# Load_Testbed.net
KiCad netlist of a schematic drawn in EAGLE
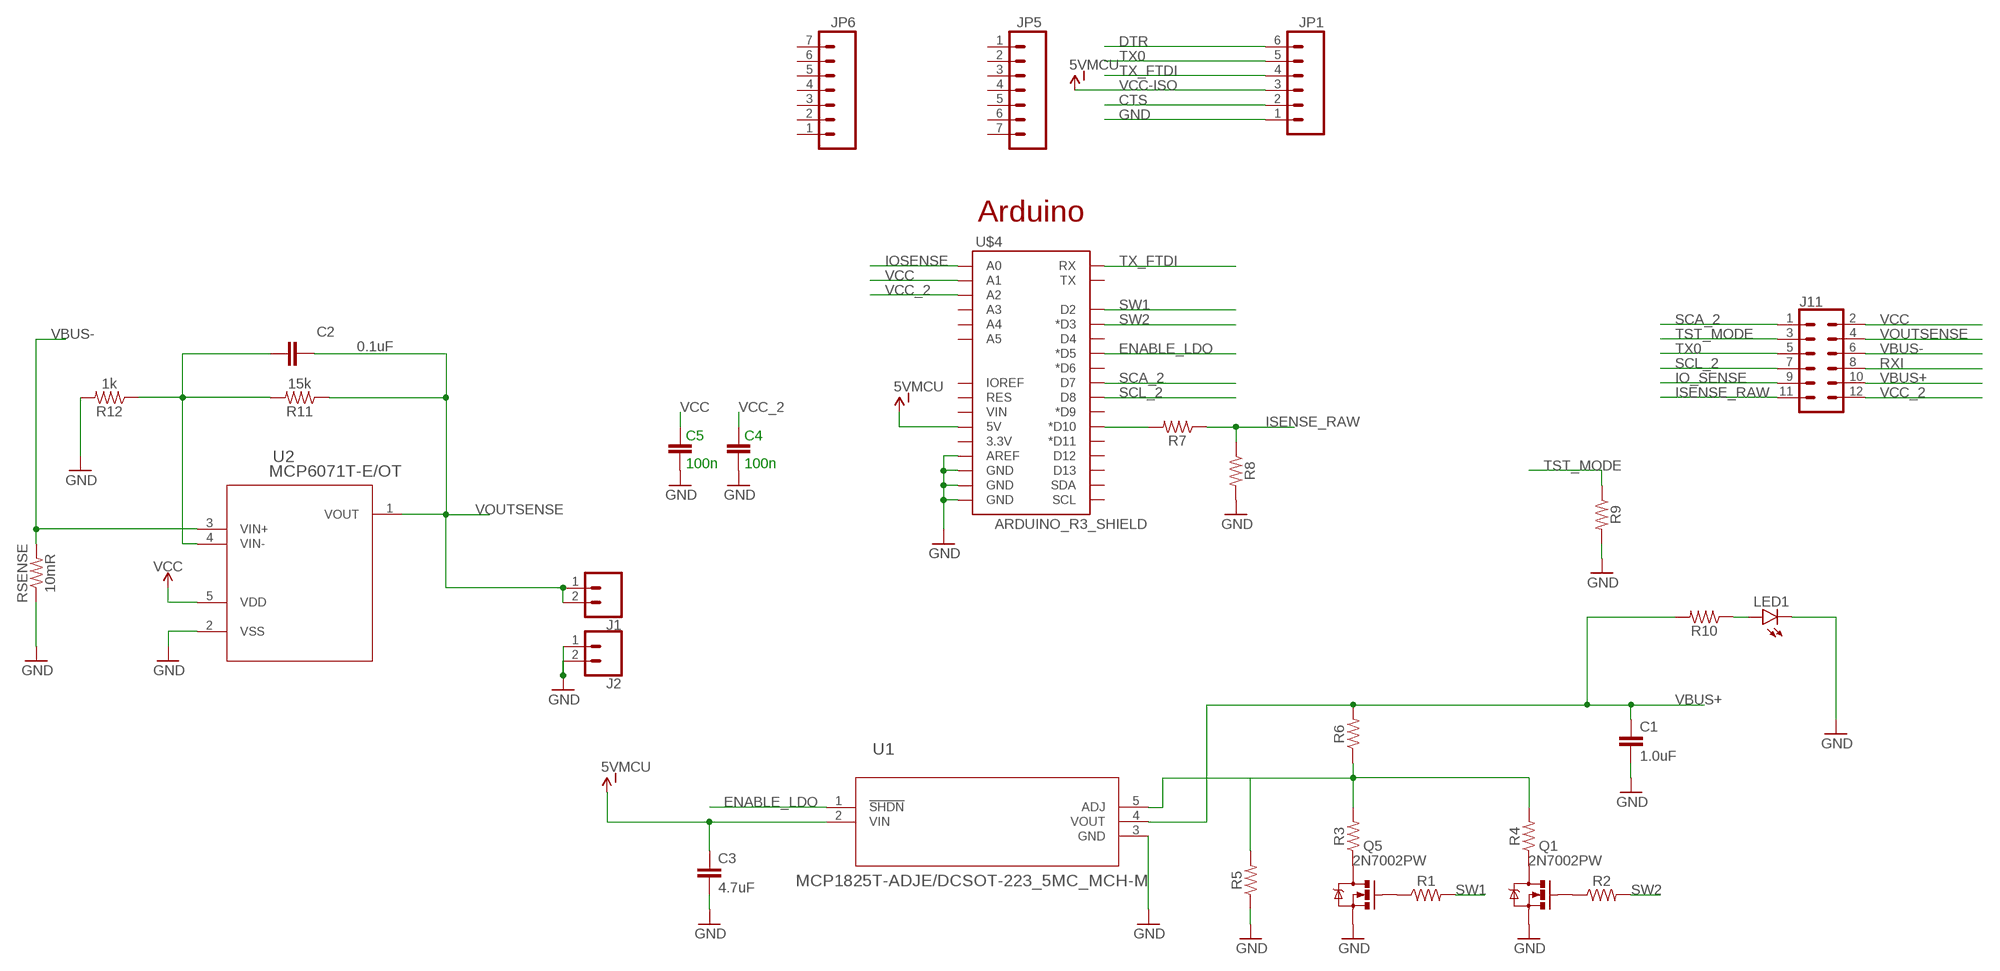
[diagram p0: schematic, sheet 1]

(export (version "E")
  (design (tool "Eeschema 10.0.6"))
  (components
    (comp (ref "C1")
      (value "1.0uF")
      (footprint "eagle-import:0805")
      (libsource (lib "eagle-import") (part "1.0UF-0805-25V-(+80/-20%)"))
    )
    (comp (ref "C2")
      (value "0.1uF")
      (footprint "eagle-import:0603")
      (libsource (lib "eagle-import") (part "0.1UF-0603-25V-(+80/-20%)"))
    )
    (comp (ref "C3")
      (value "4.7uF")
      (footprint "eagle-import:0603")
      (libsource (lib "eagle-import") (part "4.7UF0603"))
    )
    (comp (ref "C4")
      (value "100n")
      (footprint "eagle-import:0805")
      (libsource (lib "eagle-import") (part "CAP0805"))
    )
    (comp (ref "C5")
      (value "100n")
      (footprint "eagle-import:0805")
      (libsource (lib "eagle-import") (part "CAP0805"))
    )
    (comp (ref "J1")
      (value "CONN_02")
      (footprint "eagle-import:1X02")
      (libsource (lib "eagle-import") (part "CONN_02"))
    )
    (comp (ref "J2")
      (value "CONN_02")
      (footprint "eagle-import:1X02")
      (libsource (lib "eagle-import") (part "CONN_02"))
    )
    (comp (ref "J11")
      (value "2X6 FEMALE")
      (footprint "eagle-import:2X6")
      (libsource (lib "eagle-import") (part "CONN_06X2PTH_FEMALE"))
    )
    (comp (ref "JP1")
      (value "M06NO_SILK_FEMALE_PTH")
      (footprint "eagle-import:1X06_NO_SILK")
      (libsource (lib "eagle-import") (part "M06NO_SILK_FEMALE_PTH"))
    )
    (comp (ref "JP5")
      (value "M07NO_SILK")
      (footprint "eagle-import:1X07_NO_SILK")
      (libsource (lib "eagle-import") (part "M07NO_SILK"))
    )
    (comp (ref "JP6")
      (value "M07NO_SILK")
      (footprint "eagle-import:1X07_NO_SILK")
      (libsource (lib "eagle-import") (part "M07NO_SILK"))
    )
    (comp (ref "LED1")
      (value "LED3MM")
      (footprint "eagle-import:LED3MM")
      (libsource (lib "eagle-import") (part "LED3MM"))
    )
    (comp (ref "Q1")
      (value "2N7002PW")
      (footprint "eagle-import:SOT323")
      (libsource (lib "eagle-import") (part "MOSFET-NCHANNEL2N7002PW"))
    )
    (comp (ref "Q5")
      (value "2N7002PW")
      (footprint "eagle-import:SOT323")
      (libsource (lib "eagle-import") (part "MOSFET-NCHANNEL2N7002PW"))
    )
    (comp (ref "R1")
      (value "RESISTOR0805")
      (footprint "eagle-import:0805")
      (libsource (lib "eagle-import") (part "RESISTOR0805"))
    )
    (comp (ref "R2")
      (value "RESISTOR0805")
      (footprint "eagle-import:0805")
      (libsource (lib "eagle-import") (part "RESISTOR0805"))
    )
    (comp (ref "R3")
      (value "RESISTOR0805")
      (footprint "eagle-import:0805")
      (libsource (lib "eagle-import") (part "RESISTOR0805"))
    )
    (comp (ref "R4")
      (value "RESISTOR0805")
      (footprint "eagle-import:0805")
      (libsource (lib "eagle-import") (part "RESISTOR0805"))
    )
    (comp (ref "R5")
      (value "RESISTOR0805")
      (footprint "eagle-import:0805")
      (libsource (lib "eagle-import") (part "RESISTOR0805"))
    )
    (comp (ref "R6")
      (value "RESISTOR0805")
      (footprint "eagle-import:0805")
      (libsource (lib "eagle-import") (part "RESISTOR0805"))
    )
    (comp (ref "R7")
      (value "RESISTOR0805")
      (footprint "eagle-import:0805")
      (libsource (lib "eagle-import") (part "RESISTOR0805"))
    )
    (comp (ref "R8")
      (value "RESISTOR0805")
      (footprint "eagle-import:0805")
      (libsource (lib "eagle-import") (part "RESISTOR0805"))
    )
    (comp (ref "R9")
      (value "RESISTOR0805")
      (footprint "eagle-import:0805")
      (libsource (lib "eagle-import") (part "RESISTOR0805"))
    )
    (comp (ref "R10")
      (value "RESISTOR0805")
      (footprint "eagle-import:0805")
      (libsource (lib "eagle-import") (part "RESISTOR0805"))
    )
    (comp (ref "R11")
      (value "15k")
      (footprint "eagle-import:0402")
      (libsource (lib "eagle-import") (part "RESISTOR0402"))
    )
    (comp (ref "R12")
      (value "1k")
      (footprint "eagle-import:0402")
      (libsource (lib "eagle-import") (part "RESISTOR0402"))
    )
    (comp (ref "RSENSE")
      (value "10mR")
      (footprint "eagle-import:0603")
      (libsource (lib "eagle-import") (part "RESISTOR0603"))
    )
    (comp (ref "U$4")
      (value "ARDUINO_R3_SHIELD")
      (footprint "eagle-import:UNO_R3_SHIELD")
      (libsource (lib "eagle-import") (part "ARDUINO_R3_SHIELD"))
    )
    (comp (ref "U1")
      (value "MCP1825T-ADJE/DCSOT-223_5MC_MCH-M")
      (footprint "eagle-import:SOT-223_5MC_MCH-M")
      (fields (field (name "MANUFACTURER_PART_NUMBER") "MCP1825T-ADJE/DC"))
      (libsource (lib "eagle-import") (part "MCP1825T-ADJE/DCSOT-223_5MC_MCH-M"))
    )
    (comp (ref "U2")
      (value "MCP6071T-E/OT")
      (footprint "eagle-import:SOT-23-5_MC_MCH")
      (fields (field (name "COPYRIGHT") "Copyright (C) 2018 Accelerated Designs. All rights reserved"))
      (libsource (lib "eagle-import") (part "MCP6071T-E/OT"))
    )
  )
  (nets
    (net (code "1") (name "/CTS") (class "Default")
      (node (ref "JP1") (pin "2") (pinfunction "2_2") (pintype "passive"))
    )
    (net (code "2") (name "/DTR") (class "Default")
      (node (ref "JP1") (pin "6") (pinfunction "6_6") (pintype "passive"))
    )
    (net (code "3") (name "/ENABLE_LDO") (class "Default")
      (node (ref "U$4") (pin "D5") (pinfunction "*D5_D5") (pintype "bidirectional"))
      (node (ref "U1") (pin "1") (pinfunction "~{SHDN}_1") (pintype "passive"))
    )
    (net (code "4") (name "/IOSENSE") (class "Default")
      (node (ref "U$4") (pin "A0") (pinfunction "A0_A0") (pintype "bidirectional"))
    )
    (net (code "5") (name "/IO_SENSE") (class "Default")
      (node (ref "J11") (pin "9") (pinfunction "9_9") (pintype "passive"))
    )
    (net (code "6") (name "/ISENSE_RAW") (class "Default")
      (node (ref "J11") (pin "11") (pinfunction "11_11") (pintype "passive"))
      (node (ref "R7") (pin "1") (pinfunction "1_1") (pintype "passive"))
      (node (ref "R8") (pin "1") (pinfunction "1_1") (pintype "passive"))
    )
    (net (code "7") (name "/RXI") (class "Default")
      (node (ref "J11") (pin "8") (pinfunction "8_8") (pintype "passive"))
    )
    (net (code "8") (name "/SCA_2") (class "Default")
      (node (ref "J11") (pin "1") (pinfunction "1_1") (pintype "passive"))
      (node (ref "U$4") (pin "D7") (pinfunction "D7_D7") (pintype "bidirectional"))
    )
    (net (code "9") (name "/SCL_2") (class "Default")
      (node (ref "J11") (pin "7") (pinfunction "7_7") (pintype "passive"))
      (node (ref "U$4") (pin "D8") (pinfunction "D8_D8") (pintype "bidirectional"))
    )
    (net (code "10") (name "/SW1") (class "Default")
      (node (ref "R1") (pin "2") (pinfunction "2_2") (pintype "passive"))
      (node (ref "U$4") (pin "D2") (pinfunction "D2_D2") (pintype "bidirectional"))
    )
    (net (code "11") (name "/SW2") (class "Default")
      (node (ref "R2") (pin "2") (pinfunction "2_2") (pintype "passive"))
      (node (ref "U$4") (pin "D3") (pinfunction "*D3_D3") (pintype "bidirectional"))
    )
    (net (code "12") (name "/TST_MODE") (class "Default")
      (node (ref "J11") (pin "3") (pinfunction "3_3") (pintype "passive"))
      (node (ref "R9") (pin "1") (pinfunction "1_1") (pintype "passive"))
    )
    (net (code "13") (name "/TX0") (class "Default")
      (node (ref "J11") (pin "5") (pinfunction "5_5") (pintype "passive"))
      (node (ref "JP1") (pin "5") (pinfunction "5_5") (pintype "passive"))
    )
    (net (code "14") (name "/TX_FTDI") (class "Default")
      (node (ref "JP1") (pin "4") (pinfunction "4_4") (pintype "passive"))
      (node (ref "U$4") (pin "RX") (pinfunction "RX_RX") (pintype "bidirectional"))
    )
    (net (code "15") (name "/VBUS+") (class "Default")
      (node (ref "C1") (pin "1") (pinfunction "1_1") (pintype "passive"))
      (node (ref "J11") (pin "10") (pinfunction "10_10") (pintype "passive"))
      (node (ref "R10") (pin "2") (pinfunction "2_2") (pintype "passive"))
      (node (ref "R6") (pin "2") (pinfunction "2_2") (pintype "passive"))
      (node (ref "U1") (pin "4") (pinfunction "VOUT_4") (pintype "passive"))
    )
    (net (code "16") (name "/VBUS-") (class "Default")
      (node (ref "J11") (pin "6") (pinfunction "6_6") (pintype "passive"))
      (node (ref "RSENSE") (pin "2") (pinfunction "2_2") (pintype "passive"))
      (node (ref "U2") (pin "3") (pinfunction "VIN+_3") (pintype "input"))
    )
    (net (code "17") (name "/VCC_2") (class "Default")
      (node (ref "C4") (pin "2") (pinfunction "2_2") (pintype "passive"))
      (node (ref "J11") (pin "12") (pinfunction "12_12") (pintype "passive"))
      (node (ref "U$4") (pin "A2") (pinfunction "A2_A2") (pintype "bidirectional"))
    )
    (net (code "18") (name "/VOUTSENSE") (class "Default")
      (node (ref "C2") (pin "1") (pinfunction "1_1") (pintype "passive"))
      (node (ref "J1") (pin "1") (pinfunction "1_1") (pintype "passive"))
      (node (ref "J1") (pin "2") (pinfunction "2_2") (pintype "passive"))
      (node (ref "J11") (pin "4") (pinfunction "4_4") (pintype "passive"))
      (node (ref "R11") (pin "1") (pinfunction "1_1") (pintype "passive"))
      (node (ref "U2") (pin "1") (pinfunction "VOUT_1") (pintype "output"))
    )
    (net (code "19") (name "5VMCU") (class "Default")
      (node (ref "C3") (pin "1") (pinfunction "1_1") (pintype "passive"))
      (node (ref "JP1") (pin "3") (pinfunction "3_3") (pintype "passive"))
      (node (ref "U$4") (pin "5V") (pinfunction "5V_5V") (pintype "bidirectional"))
      (node (ref "U1") (pin "2") (pinfunction "VIN_2") (pintype "passive"))
    )
    (net (code "20") (name "GND") (class "Default")
      (node (ref "C1") (pin "2") (pinfunction "2_2") (pintype "passive"))
      (node (ref "C3") (pin "2") (pinfunction "2_2") (pintype "passive"))
      (node (ref "C4") (pin "1") (pinfunction "1_1") (pintype "passive"))
      (node (ref "C5") (pin "1") (pinfunction "1_1") (pintype "passive"))
      (node (ref "J2") (pin "1") (pinfunction "1_1") (pintype "passive"))
      (node (ref "J2") (pin "2") (pinfunction "2_2") (pintype "passive"))
      (node (ref "JP1") (pin "1") (pinfunction "1_1") (pintype "passive"))
      (node (ref "LED1") (pin "K") (pinfunction "C_K") (pintype "passive"))
      (node (ref "Q1") (pin "2") (pinfunction "S_2") (pintype "passive"))
      (node (ref "Q5") (pin "2") (pinfunction "S_2") (pintype "passive"))
      (node (ref "R12") (pin "2") (pinfunction "2_2") (pintype "passive"))
      (node (ref "R5") (pin "1") (pinfunction "1_1") (pintype "passive"))
      (node (ref "R8") (pin "2") (pinfunction "2_2") (pintype "passive"))
      (node (ref "R9") (pin "2") (pinfunction "2_2") (pintype "passive"))
      (node (ref "RSENSE") (pin "1") (pinfunction "1_1") (pintype "passive"))
      (node (ref "U$4") (pin "AREF") (pinfunction "AREF_AREF") (pintype "bidirectional"))
      (node (ref "U$4") (pin "GND@0") (pinfunction "GND_GND@0") (pintype "bidirectional"))
      (node (ref "U$4") (pin "GND@1") (pinfunction "GND_GND@1") (pintype "bidirectional"))
      (node (ref "U$4") (pin "GND@2") (pinfunction "GND_GND@2") (pintype "bidirectional"))
      (node (ref "U1") (pin "3") (pinfunction "GND_3") (pintype "passive"))
      (node (ref "U2") (pin "2") (pinfunction "VSS_2") (pintype "power_in"))
    )
    (net (code "21") (name "Net-(LED1-PadA)") (class "Default")
      (node (ref "LED1") (pin "A") (pinfunction "A_A") (pintype "passive"))
      (node (ref "R10") (pin "1") (pinfunction "1_1") (pintype "passive"))
    )
    (net (code "22") (name "Net-(Q1-D)") (class "Default")
      (node (ref "Q1") (pin "3") (pinfunction "D_3") (pintype "passive"))
      (node (ref "R4") (pin "1") (pinfunction "1_1") (pintype "passive"))
    )
    (net (code "23") (name "Net-(Q1-G)") (class "Default")
      (node (ref "Q1") (pin "1") (pinfunction "G_1") (pintype "passive"))
      (node (ref "R2") (pin "1") (pinfunction "1_1") (pintype "passive"))
    )
    (net (code "24") (name "Net-(Q5-D)") (class "Default")
      (node (ref "Q5") (pin "3") (pinfunction "D_3") (pintype "passive"))
      (node (ref "R3") (pin "1") (pinfunction "1_1") (pintype "passive"))
    )
    (net (code "25") (name "Net-(Q5-G)") (class "Default")
      (node (ref "Q5") (pin "1") (pinfunction "G_1") (pintype "passive"))
      (node (ref "R1") (pin "1") (pinfunction "1_1") (pintype "passive"))
    )
    (net (code "26") (name "Net-(U$4-*D10)") (class "Default")
      (node (ref "R7") (pin "2") (pinfunction "2_2") (pintype "passive"))
      (node (ref "U$4") (pin "D10") (pinfunction "*D10_D10") (pintype "bidirectional"))
    )
    (net (code "27") (name "Net-(U1-ADJ)") (class "Default")
      (node (ref "R3") (pin "2") (pinfunction "2_2") (pintype "passive"))
      (node (ref "R4") (pin "2") (pinfunction "2_2") (pintype "passive"))
      (node (ref "R5") (pin "2") (pinfunction "2_2") (pintype "passive"))
      (node (ref "R6") (pin "1") (pinfunction "1_1") (pintype "passive"))
      (node (ref "U1") (pin "5") (pinfunction "ADJ_5") (pintype "passive"))
    )
    (net (code "28") (name "Net-(U2-VIN-)") (class "Default")
      (node (ref "C2") (pin "2") (pinfunction "2_2") (pintype "passive"))
      (node (ref "R11") (pin "2") (pinfunction "2_2") (pintype "passive"))
      (node (ref "R12") (pin "1") (pinfunction "1_1") (pintype "passive"))
      (node (ref "U2") (pin "4") (pinfunction "VIN-_4") (pintype "input"))
    )
    (net (code "29") (name "VCC") (class "Default")
      (node (ref "C5") (pin "2") (pinfunction "2_2") (pintype "passive"))
      (node (ref "J11") (pin "2") (pinfunction "2_2") (pintype "passive"))
      (node (ref "U$4") (pin "A1") (pinfunction "A1_A1") (pintype "bidirectional"))
      (node (ref "U2") (pin "5") (pinfunction "VDD_5") (pintype "power_in"))
    )
    (net (code "30") (name "unconnected-(JP5-Pad1)") (class "Default")
      (node (ref "JP5") (pin "1") (pinfunction "1_1") (pintype "passive"))
    )
    (net (code "31") (name "unconnected-(JP5-Pad2)") (class "Default")
      (node (ref "JP5") (pin "2") (pinfunction "2_2") (pintype "passive"))
    )
    (net (code "32") (name "unconnected-(JP5-Pad3)") (class "Default")
      (node (ref "JP5") (pin "3") (pinfunction "3_3") (pintype "passive"))
    )
    (net (code "33") (name "unconnected-(JP5-Pad4)") (class "Default")
      (node (ref "JP5") (pin "4") (pinfunction "4_4") (pintype "passive"))
    )
    (net (code "34") (name "unconnected-(JP5-Pad5)") (class "Default")
      (node (ref "JP5") (pin "5") (pinfunction "5_5") (pintype "passive"))
    )
    (net (code "35") (name "unconnected-(JP5-Pad6)") (class "Default")
      (node (ref "JP5") (pin "6") (pinfunction "6_6") (pintype "passive"))
    )
    (net (code "36") (name "unconnected-(JP5-Pad7)") (class "Default")
      (node (ref "JP5") (pin "7") (pinfunction "7_7") (pintype "passive"))
    )
    (net (code "37") (name "unconnected-(JP6-Pad1)") (class "Default")
      (node (ref "JP6") (pin "1") (pinfunction "1_1") (pintype "passive"))
    )
    (net (code "38") (name "unconnected-(JP6-Pad2)") (class "Default")
      (node (ref "JP6") (pin "2") (pinfunction "2_2") (pintype "passive"))
    )
    (net (code "39") (name "unconnected-(JP6-Pad3)") (class "Default")
      (node (ref "JP6") (pin "3") (pinfunction "3_3") (pintype "passive"))
    )
    (net (code "40") (name "unconnected-(JP6-Pad4)") (class "Default")
      (node (ref "JP6") (pin "4") (pinfunction "4_4") (pintype "passive"))
    )
    (net (code "41") (name "unconnected-(JP6-Pad5)") (class "Default")
      (node (ref "JP6") (pin "5") (pinfunction "5_5") (pintype "passive"))
    )
    (net (code "42") (name "unconnected-(JP6-Pad6)") (class "Default")
      (node (ref "JP6") (pin "6") (pinfunction "6_6") (pintype "passive"))
    )
    (net (code "43") (name "unconnected-(JP6-Pad7)") (class "Default")
      (node (ref "JP6") (pin "7") (pinfunction "7_7") (pintype "passive"))
    )
    (net (code "44") (name "unconnected-(U$4-*D6-PadD6)") (class "Default")
      (node (ref "U$4") (pin "D6") (pinfunction "*D6_D6") (pintype "bidirectional"))
    )
    (net (code "45") (name "unconnected-(U$4-*D9-PadD9)") (class "Default")
      (node (ref "U$4") (pin "D9") (pinfunction "*D9_D9") (pintype "bidirectional"))
    )
    (net (code "46") (name "unconnected-(U$4-*D11-PadD11)") (class "Default")
      (node (ref "U$4") (pin "D11") (pinfunction "*D11_D11") (pintype "bidirectional"))
    )
    (net (code "47") (name "unconnected-(U$4-Pad3.3V)") (class "Default")
      (node (ref "U$4") (pin "3.3V") (pinfunction "3.3V_3.3V") (pintype "bidirectional"))
    )
    (net (code "48") (name "unconnected-(U$4-PadA3)") (class "Default")
      (node (ref "U$4") (pin "A3") (pinfunction "A3_A3") (pintype "bidirectional"))
    )
    (net (code "49") (name "unconnected-(U$4-PadA4)") (class "Default")
      (node (ref "U$4") (pin "A4") (pinfunction "A4_A4") (pintype "bidirectional"))
    )
    (net (code "50") (name "unconnected-(U$4-PadA5)") (class "Default")
      (node (ref "U$4") (pin "A5") (pinfunction "A5_A5") (pintype "bidirectional"))
    )
    (net (code "51") (name "unconnected-(U$4-PadD4)") (class "Default")
      (node (ref "U$4") (pin "D4") (pinfunction "D4_D4") (pintype "bidirectional"))
    )
    (net (code "52") (name "unconnected-(U$4-PadD12)") (class "Default")
      (node (ref "U$4") (pin "D12") (pinfunction "D12_D12") (pintype "bidirectional"))
    )
    (net (code "53") (name "unconnected-(U$4-PadD13)") (class "Default")
      (node (ref "U$4") (pin "D13") (pinfunction "D13_D13") (pintype "bidirectional"))
    )
    (net (code "54") (name "unconnected-(U$4-PadIOREF)") (class "Default")
      (node (ref "U$4") (pin "IOREF") (pinfunction "IOREF_IOREF") (pintype "bidirectional"))
    )
    (net (code "55") (name "unconnected-(U$4-PadRES)") (class "Default")
      (node (ref "U$4") (pin "RES") (pinfunction "RES_RES") (pintype "bidirectional"))
    )
    (net (code "56") (name "unconnected-(U$4-PadSCL)") (class "Default")
      (node (ref "U$4") (pin "SCL") (pinfunction "SCL_SCL") (pintype "bidirectional"))
    )
    (net (code "57") (name "unconnected-(U$4-PadSDA)") (class "Default")
      (node (ref "U$4") (pin "SDA") (pinfunction "SDA_SDA") (pintype "bidirectional"))
    )
    (net (code "58") (name "unconnected-(U$4-PadTX)") (class "Default")
      (node (ref "U$4") (pin "TX") (pinfunction "TX_TX") (pintype "bidirectional"))
    )
    (net (code "59") (name "unconnected-(U$4-PadVIN)") (class "Default")
      (node (ref "U$4") (pin "VIN") (pinfunction "VIN_VIN") (pintype "bidirectional"))
    )
  )
)
